# Schematic_Main_Board.net
KiCad netlist of a schematic drawn in Altium Designer
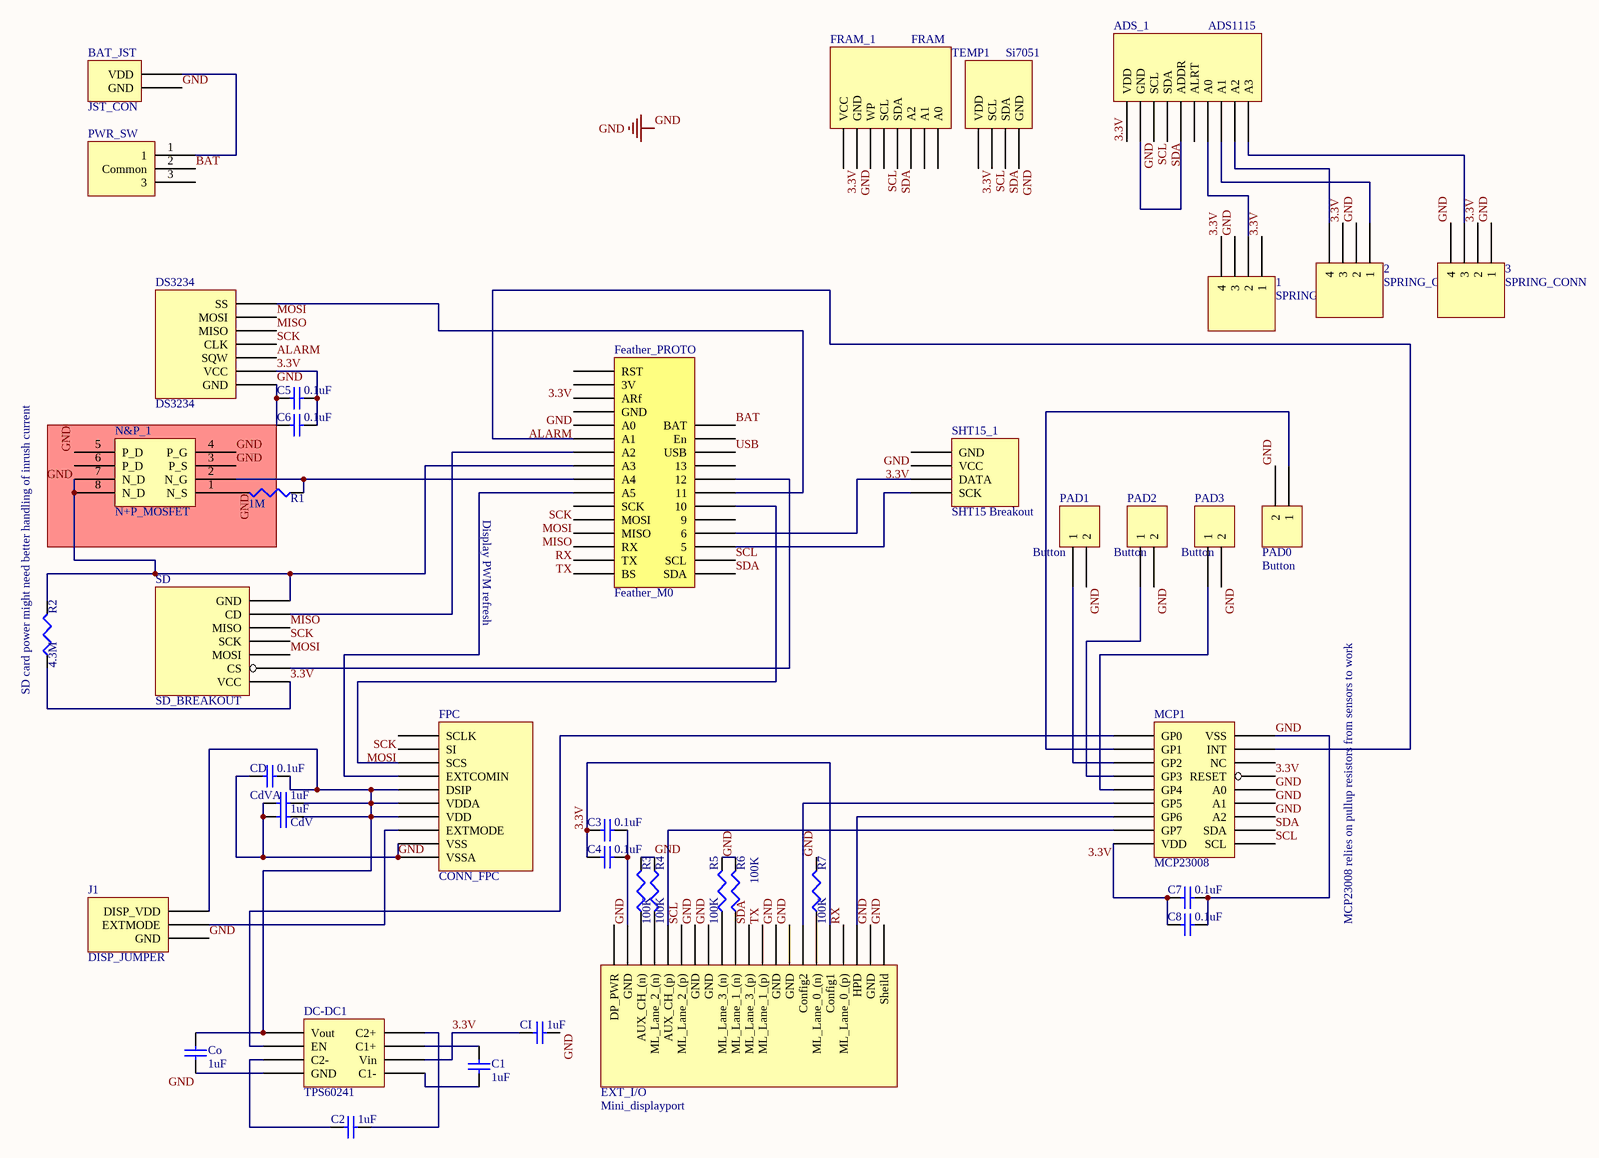
[diagram p0: Schematic_Main_Board.SchDoc]

(export (version "E")
  (design (tool "Eeschema 10.0.6"))
  (components
    (comp (ref "1")
      (value "SPRING_CONN")
      (footprint "QUICK_CONN")
      (libsource (lib "Parts_Schematic") (part "SPRING_CONN"))
    )
    (comp (ref "2")
      (value "SPRING_CONN")
      (footprint "QUICK_CONN")
      (libsource (lib "Parts_Schematic") (part "SPRING_CONN"))
    )
    (comp (ref "3")
      (value "SPRING_CONN")
      (footprint "QUICK_CONN")
      (libsource (lib "Parts_Schematic") (part "SPRING_CONN"))
    )
    (comp (ref "ADS_1")
      (value "ADS1115")
      (footprint "ADS1115")
      (libsource (lib "Parts_Schematic") (part "ADS1115"))
    )
    (comp (ref "BAT_JST")
      (value "JST_CON")
      (footprint "JST_CONN")
      (libsource (lib "Parts_Schematic") (part "JST_CON"))
    )
    (comp (ref "C1")
      (value "1uF")
      (footprint "C0805")
      (description "Capacitor (Semiconductor SIM Model)")
      (fields (field (name "Comment") "Cap Semi") (field (name "PUBLISHER") "Altium Limited"))
      (libsource (lib "Miscellaneous Devices") (part "Cap Semi"))
    )
    (comp (ref "C2")
      (value "1uF")
      (footprint "C0805")
      (description "Capacitor (Semiconductor SIM Model)")
      (fields (field (name "Comment") "Cap Semi") (field (name "PUBLISHER") "Altium Limited"))
      (libsource (lib "Miscellaneous Devices") (part "Cap Semi"))
    )
    (comp (ref "C3")
      (value "0.1uF")
      (footprint "C0805")
      (description "Capacitor (Semiconductor SIM Model)")
      (fields (field (name "Comment") "Cap Semi") (field (name "PUBLISHER") "Altium Limited"))
      (libsource (lib "Miscellaneous Devices") (part "Cap Semi"))
    )
    (comp (ref "C4")
      (value "0.1uF")
      (footprint "C0805")
      (description "Capacitor (Semiconductor SIM Model)")
      (fields (field (name "Comment") "Cap Semi") (field (name "PUBLISHER") "Altium Limited"))
      (libsource (lib "Miscellaneous Devices") (part "Cap Semi"))
    )
    (comp (ref "C5")
      (value "0.1uF")
      (footprint "C0805")
      (description "Capacitor (Semiconductor SIM Model)")
      (fields (field (name "Comment") "Cap Semi") (field (name "PUBLISHER") "Altium Limited"))
      (libsource (lib "Miscellaneous Devices") (part "Cap Semi"))
    )
    (comp (ref "C6")
      (value "0.1uF")
      (footprint "C0805")
      (description "Capacitor (Semiconductor SIM Model)")
      (fields (field (name "Comment") "Cap Semi") (field (name "PUBLISHER") "Altium Limited"))
      (libsource (lib "Miscellaneous Devices") (part "Cap Semi"))
    )
    (comp (ref "C7")
      (value "0.1uF")
      (footprint "C0805")
      (description "Capacitor (Semiconductor SIM Model)")
      (fields (field (name "Comment") "Cap Semi") (field (name "PUBLISHER") "Altium Limited"))
      (libsource (lib "Miscellaneous Devices") (part "Cap Semi"))
    )
    (comp (ref "C8")
      (value "0.1uF")
      (footprint "C0805")
      (description "Capacitor (Semiconductor SIM Model)")
      (fields (field (name "Comment") "Cap Semi") (field (name "PUBLISHER") "Altium Limited"))
      (libsource (lib "Miscellaneous Devices") (part "Cap Semi"))
    )
    (comp (ref "CD")
      (value "0.1uF")
      (footprint "C0805")
      (description "Capacitor (Semiconductor SIM Model)")
      (fields (field (name "Comment") "Cap Semi") (field (name "PUBLISHER") "Altium Limited"))
      (libsource (lib "Miscellaneous Devices") (part "Cap Semi"))
    )
    (comp (ref "CdV")
      (value "1uF")
      (footprint "C0805")
      (description "Capacitor (Semiconductor SIM Model)")
      (fields (field (name "Comment") "Cap Semi") (field (name "PUBLISHER") "Altium Limited"))
      (libsource (lib "Miscellaneous Devices") (part "Cap Semi"))
    )
    (comp (ref "CdVA")
      (value "1uF")
      (footprint "C0805")
      (description "Capacitor (Semiconductor SIM Model)")
      (fields (field (name "Comment") "Cap Semi") (field (name "PUBLISHER") "Altium Limited"))
      (libsource (lib "Miscellaneous Devices") (part "Cap Semi"))
    )
    (comp (ref "CI")
      (value "1uF")
      (footprint "C0805")
      (description "Capacitor (Semiconductor SIM Model)")
      (fields (field (name "Comment") "Cap Semi") (field (name "PUBLISHER") "Altium Limited"))
      (libsource (lib "Miscellaneous Devices") (part "Cap Semi"))
    )
    (comp (ref "Co")
      (value "1uF")
      (footprint "C0805")
      (description "Capacitor (Semiconductor SIM Model)")
      (fields (field (name "Comment") "Cap Semi") (field (name "PUBLISHER") "Altium Limited"))
      (libsource (lib "Miscellaneous Devices") (part "Cap Semi"))
    )
    (comp (ref "DC-DC1")
      (value "TPS60241")
      (footprint "TPS60241")
      (libsource (lib "Parts_Schematic") (part "TPS60241"))
    )
    (comp (ref "DS3234")
      (value "DS3234")
      (footprint "DS3234_FOOTPRINT")
      (libsource (lib "Parts_Schematic") (part "DS3234"))
    )
    (comp (ref "EXT_I/O")
      (value "Mini_displayport")
      (footprint "CONN_Displayport")
      (libsource (lib "Parts_Schematic") (part "Mini_displayport"))
    )
    (comp (ref "Feather_PROTO")
      (value "Feather_M0")
      (footprint "Feather_M0")
      (libsource (lib "Parts_Schematic") (part "Feather_M0"))
    )
    (comp (ref "FPC")
      (value "CONN_FPC")
      (footprint "CONN_FPC")
      (libsource (lib "Parts_Schematic") (part "CONN_FPC"))
    )
    (comp (ref "FRAM_1") (value "FRAM") (footprint "FRAM") (libsource (lib "Parts_Schematic") (part "FRAM")))
    (comp (ref "J1")
      (value "DISP_JUMPER")
      (footprint "DISP_Jumper")
      (libsource (lib "Parts_Schematic") (part "DISP_JUMPER"))
    )
    (comp (ref "MCP1")
      (value "MCP23008")
      (footprint "MCP23008")
      (libsource (lib "Parts_Schematic") (part "MCP23008"))
    )
    (comp (ref "N&P_1")
      (value "N+P_MOSFET")
      (footprint "SOP8")
      (libsource (lib "Parts_Schematic") (part "N+P_MOSFET"))
    )
    (comp (ref "PAD0") (value "Button") (footprint "Button_footprint") (libsource (lib "") (part "Button_1")))
    (comp (ref "PAD1")
      (value "Button")
      (footprint "Button_footprint")
      (libsource (lib "Parts_Schematic") (part "Button"))
    )
    (comp (ref "PAD2")
      (value "Button")
      (footprint "Button_footprint")
      (libsource (lib "Parts_Schematic") (part "Button"))
    )
    (comp (ref "PAD3")
      (value "Button")
      (footprint "Button_footprint")
      (libsource (lib "Parts_Schematic") (part "Button"))
    )
    (comp (ref "PWR_SW")
      (value "Switch")
      (footprint "Switch_footprint")
      (libsource (lib "Parts_Schematic") (part "Switch"))
    )
    (comp (ref "R1")
      (value "1M")
      (footprint "6-0805_N")
      (description "Resistor")
      (fields (field (name "Comment") "Res3") (field (name "PUBLISHER") "Altium Limited"))
      (libsource (lib "Miscellaneous Devices") (part "Res3"))
    )
    (comp (ref "R2")
      (value "4.3M")
      (footprint "6-0805_N")
      (description "Resistor")
      (fields (field (name "Comment") "Res3") (field (name "PUBLISHER") "Altium Limited"))
      (libsource (lib "Miscellaneous Devices") (part "Res3"))
    )
    (comp (ref "R3")
      (value "100K")
      (footprint "6-0805_N")
      (description "Resistor")
      (fields (field (name "Comment") "Res3") (field (name "PUBLISHER") "Altium Limited"))
      (libsource (lib "Miscellaneous Devices") (part "Res3"))
    )
    (comp (ref "R4")
      (value "100K")
      (footprint "6-0805_N")
      (description "Resistor")
      (fields (field (name "Comment") "Res3") (field (name "PUBLISHER") "Altium Limited"))
      (libsource (lib "Miscellaneous Devices") (part "Res3"))
    )
    (comp (ref "R5")
      (value "100K")
      (footprint "6-0805_N")
      (description "Resistor")
      (fields (field (name "Comment") "Res3") (field (name "PUBLISHER") "Altium Limited"))
      (libsource (lib "Miscellaneous Devices") (part "Res3"))
    )
    (comp (ref "R6")
      (value "100K")
      (footprint "6-0805_N")
      (description "Resistor")
      (fields (field (name "Comment") "Res3") (field (name "PUBLISHER") "Altium Limited"))
      (libsource (lib "Miscellaneous Devices") (part "Res3"))
    )
    (comp (ref "R7")
      (value "100K")
      (footprint "6-0805_N")
      (description "Resistor")
      (fields (field (name "Comment") "Res3") (field (name "PUBLISHER") "Altium Limited"))
      (libsource (lib "Miscellaneous Devices") (part "Res3"))
    )
    (comp (ref "SD")
      (value "SD_BREAKOUT")
      (footprint "SD_BREAKOUT_FOOTPRINT")
      (libsource (lib "Parts_Schematic") (part "SD_BREAKOUT"))
    )
    (comp (ref "SHT15_1")
      (value "SHT15 Breakout")
      (footprint "SHT15_BREAKOUT_FOOTPRINT")
      (libsource (lib "Parts_Schematic") (part "SHT15_BREAKOUT"))
    )
    (comp (ref "TEMP1")
      (value "Si7051")
      (footprint "Si7051_Footprint")
      (libsource (lib "Parts_Schematic") (part "Si7051"))
    )
  )
  (nets
    (net (code "1") (name "/3.3V") (class "Default")
      (node (ref "1") (pin "1") (pinfunction "1_1") (pintype "passive"))
      (node (ref "1") (pin "4") (pinfunction "4_4") (pintype "passive"))
      (node (ref "2") (pin "3") (pinfunction "3_3") (pintype "passive"))
      (node (ref "3") (pin "2") (pinfunction "2_2") (pintype "passive"))
      (node (ref "ADS_1") (pin "1") (pinfunction "VDD_1") (pintype "passive"))
      (node (ref "C3") (pin "1") (pinfunction "1_1") (pintype "passive"))
      (node (ref "C4") (pin "2") (pinfunction "2_2") (pintype "passive"))
      (node (ref "C5") (pin "2") (pinfunction "2_2") (pintype "passive"))
      (node (ref "C6") (pin "1") (pinfunction "1_1") (pintype "passive"))
      (node (ref "C7") (pin "1") (pinfunction "1_1") (pintype "passive"))
      (node (ref "C8") (pin "2") (pinfunction "2_2") (pintype "passive"))
      (node (ref "CI") (pin "2") (pinfunction "2_2") (pintype "passive"))
      (node (ref "DC-DC1") (pin "6") (pinfunction "Vin_6") (pintype "passive"))
      (node (ref "DS3234") (pin "2") (pinfunction "VCC_2") (pintype "passive"))
      (node (ref "EXT_I/O") (pin "4") (pinfunction "Config1_4") (pintype "passive"))
      (node (ref "FRAM_1") (pin "1") (pinfunction "VCC_1") (pintype "passive"))
      (node (ref "Feather_PROTO") (pin "2") (pinfunction "3V_2") (pintype "passive"))
      (node (ref "MCP1") (pin "18") (pinfunction "VDD_18") (pintype "passive"))
      (node (ref "MCP1") (pin "6") (pinfunction "RESET_6") (pintype "passive"))
      (node (ref "R2") (pin "1") (pinfunction "1_1") (pintype "passive"))
      (node (ref "SD") (pin "1") (pinfunction "VCC_1") (pintype "passive"))
      (node (ref "SHT15_1") (pin "2") (pinfunction "VCC_2") (pintype "passive"))
      (node (ref "TEMP1") (pin "1") (pinfunction "VDD_1") (pintype "passive"))
    )
    (net (code "2") (name "/ALARM") (class "Default")
      (node (ref "DS3234") (pin "3") (pinfunction "SQW_3") (pintype "passive"))
      (node (ref "Feather_PROTO") (pin "5") (pinfunction "A0_5") (pintype "passive"))
    )
    (net (code "3") (name "/BAT") (class "Default")
      (node (ref "Feather_PROTO") (pin "28") (pinfunction "BAT_28") (pintype "passive"))
      (node (ref "PWR_SW") (pin "2") (pinfunction "Common_2") (pintype "passive"))
    )
    (net (code "4") (name "/MISO") (class "Default")
      (node (ref "DS3234") (pin "5") (pinfunction "MISO_5") (pintype "passive"))
      (node (ref "Feather_PROTO") (pin "13") (pinfunction "MISO_13") (pintype "passive"))
      (node (ref "SD") (pin "5") (pinfunction "MISO_5") (pintype "passive"))
    )
    (net (code "5") (name "/MOSI") (class "Default")
      (node (ref "DS3234") (pin "6") (pinfunction "MOSI_6") (pintype "passive"))
      (node (ref "FPC") (pin "2") (pinfunction "SI_2") (pintype "passive"))
      (node (ref "Feather_PROTO") (pin "12") (pinfunction "MOSI_12") (pintype "passive"))
      (node (ref "SD") (pin "3") (pinfunction "MOSI_3") (pintype "passive"))
    )
    (net (code "6") (name "/RX") (class "Default")
      (node (ref "EXT_I/O") (pin "3") (pinfunction "ML_Lane_0_(p)_3") (pintype "passive"))
      (node (ref "Feather_PROTO") (pin "14") (pinfunction "RX_14") (pintype "passive"))
    )
    (net (code "7") (name "/SCK") (class "Default")
      (node (ref "DS3234") (pin "4") (pinfunction "CLK_4") (pintype "passive"))
      (node (ref "FPC") (pin "1") (pinfunction "SCLK_1") (pintype "passive"))
      (node (ref "Feather_PROTO") (pin "11") (pinfunction "SCK_11") (pintype "passive"))
      (node (ref "SD") (pin "4") (pinfunction "SCK_4") (pintype "passive"))
    )
    (net (code "8") (name "/SCL") (class "Default")
      (node (ref "ADS_1") (pin "3") (pinfunction "SCL_3") (pintype "passive"))
      (node (ref "EXT_I/O") (pin "15") (pinfunction "ML_Lane_2_(p)_15") (pintype "passive"))
      (node (ref "FRAM_1") (pin "4") (pinfunction "SCL_4") (pintype "passive"))
      (node (ref "Feather_PROTO") (pin "18") (pinfunction "SCL_18") (pintype "passive"))
      (node (ref "MCP1") (pin "1") (pinfunction "SCL_1") (pintype "passive"))
      (node (ref "TEMP1") (pin "2") (pinfunction "SCL_2") (pintype "passive"))
    )
    (net (code "9") (name "/SDA") (class "Default")
      (node (ref "ADS_1") (pin "4") (pinfunction "SDA_4") (pintype "passive"))
      (node (ref "EXT_I/O") (pin "10") (pinfunction "ML_Lane_3_(p)_10") (pintype "passive"))
      (node (ref "FRAM_1") (pin "5") (pinfunction "SDA_5") (pintype "passive"))
      (node (ref "Feather_PROTO") (pin "17") (pinfunction "SDA_17") (pintype "passive"))
      (node (ref "MCP1") (pin "2") (pinfunction "SDA_2") (pintype "passive"))
      (node (ref "TEMP1") (pin "3") (pinfunction "SDA_3") (pintype "passive"))
    )
    (net (code "10") (name "/TX") (class "Default")
      (node (ref "EXT_I/O") (pin "9") (pinfunction "ML_Lane_1_(p)_9") (pintype "passive"))
      (node (ref "Feather_PROTO") (pin "15") (pinfunction "TX_15") (pintype "passive"))
    )
    (net (code "11") (name "/USB") (class "Default")
      (node (ref "Feather_PROTO") (pin "26") (pinfunction "USB_26") (pintype "passive"))
    )
    (net (code "12") (name "GND") (class "Default")
      (node (ref "1") (pin "3") (pinfunction "3_3") (pintype "passive"))
      (node (ref "2") (pin "2") (pinfunction "2_2") (pintype "passive"))
      (node (ref "3") (pin "1") (pinfunction "1_1") (pintype "passive"))
      (node (ref "3") (pin "4") (pinfunction "4_4") (pintype "passive"))
      (node (ref "ADS_1") (pin "2") (pinfunction "GND_2") (pintype "passive"))
      (node (ref "ADS_1") (pin "5") (pinfunction "ADDR_5") (pintype "passive"))
      (node (ref "BAT_JST") (pin "1") (pinfunction "GND_1") (pintype "passive"))
      (node (ref "C3") (pin "2") (pinfunction "2_2") (pintype "passive"))
      (node (ref "C4") (pin "1") (pinfunction "1_1") (pintype "passive"))
      (node (ref "C5") (pin "1") (pinfunction "1_1") (pintype "passive"))
      (node (ref "C6") (pin "2") (pinfunction "2_2") (pintype "passive"))
      (node (ref "C7") (pin "2") (pinfunction "2_2") (pintype "passive"))
      (node (ref "C8") (pin "1") (pinfunction "1_1") (pintype "passive"))
      (node (ref "CD") (pin "2") (pinfunction "2_2") (pintype "passive"))
      (node (ref "CI") (pin "1") (pinfunction "1_1") (pintype "passive"))
      (node (ref "CdV") (pin "2") (pinfunction "2_2") (pintype "passive"))
      (node (ref "CdVA") (pin "2") (pinfunction "2_2") (pintype "passive"))
      (node (ref "Co") (pin "2") (pinfunction "2_2") (pintype "passive"))
      (node (ref "DC-DC1") (pin "4") (pinfunction "GND_4") (pintype "passive"))
      (node (ref "DS3234") (pin "1") (pinfunction "GND_1") (pintype "passive"))
      (node (ref "EXT_I/O") (pin "0") (pinfunction "Sheild_0") (pintype "passive"))
      (node (ref "EXT_I/O") (pin "1") (pinfunction "GND_1") (pintype "passive"))
      (node (ref "EXT_I/O") (pin "13") (pinfunction "GND_13") (pintype "passive"))
      (node (ref "EXT_I/O") (pin "14") (pinfunction "GND_14") (pintype "passive"))
      (node (ref "EXT_I/O") (pin "19") (pinfunction "GND_19") (pintype "passive"))
      (node (ref "EXT_I/O") (pin "7") (pinfunction "GND_7") (pintype "passive"))
      (node (ref "EXT_I/O") (pin "8") (pinfunction "GND_8") (pintype "passive"))
      (node (ref "FPC") (pin "10") (pinfunction "VSSA_10") (pintype "passive"))
      (node (ref "FPC") (pin "9") (pinfunction "VSS_9") (pintype "passive"))
      (node (ref "FRAM_1") (pin "2") (pinfunction "GND_2") (pintype "passive"))
      (node (ref "Feather_PROTO") (pin "4") (pinfunction "GND_4") (pintype "passive"))
      (node (ref "J1") (pin "1") (pinfunction "GND_1") (pintype "passive"))
      (node (ref "MCP1") (pin "3") (pinfunction "A2_3") (pintype "passive"))
      (node (ref "MCP1") (pin "4") (pinfunction "A1_4") (pintype "passive"))
      (node (ref "MCP1") (pin "5") (pinfunction "A0_5") (pintype "passive"))
      (node (ref "MCP1") (pin "9") (pinfunction "VSS_9") (pintype "passive"))
      (node (ref "N&P_1") (pin "1") (pinfunction "N_S_1") (pintype "passive"))
      (node (ref "N&P_1") (pin "3") (pinfunction "P_S_3") (pintype "passive"))
      (node (ref "N&P_1") (pin "4") (pinfunction "P_G_4") (pintype "passive"))
      (node (ref "N&P_1") (pin "5") (pinfunction "P_D_5") (pintype "passive"))
      (node (ref "N&P_1") (pin "6") (pinfunction "P_D_6") (pintype "passive"))
      (node (ref "PAD0") (pin "2") (pinfunction "2_2") (pintype "passive"))
      (node (ref "PAD1") (pin "2") (pinfunction "2_2") (pintype "passive"))
      (node (ref "PAD2") (pin "2") (pinfunction "2_2") (pintype "passive"))
      (node (ref "PAD3") (pin "2") (pinfunction "2_2") (pintype "passive"))
      (node (ref "R1") (pin "2") (pinfunction "2_2") (pintype "passive"))
      (node (ref "R3") (pin "2") (pinfunction "2_2") (pintype "passive"))
      (node (ref "R4") (pin "1") (pinfunction "1_1") (pintype "passive"))
      (node (ref "R5") (pin "2") (pinfunction "2_2") (pintype "passive"))
      (node (ref "R6") (pin "2") (pinfunction "2_2") (pintype "passive"))
      (node (ref "R7") (pin "2") (pinfunction "2_2") (pintype "passive"))
      (node (ref "SHT15_1") (pin "1") (pinfunction "GND_1") (pintype "passive"))
      (node (ref "TEMP1") (pin "4") (pinfunction "GND_4") (pintype "passive"))
    )
    (net (code "13") (name "Net-(ADS_1-A0)") (class "Default")
      (node (ref "1") (pin "2") (pinfunction "2_2") (pintype "passive"))
      (node (ref "ADS_1") (pin "7") (pinfunction "A0_7") (pintype "passive"))
    )
    (net (code "14") (name "Net-(ADS_1-A1)") (class "Default")
      (node (ref "2") (pin "1") (pinfunction "1_1") (pintype "passive"))
      (node (ref "ADS_1") (pin "8") (pinfunction "A1_8") (pintype "passive"))
    )
    (net (code "15") (name "Net-(ADS_1-A2)") (class "Default")
      (node (ref "2") (pin "4") (pinfunction "4_4") (pintype "passive"))
      (node (ref "ADS_1") (pin "9") (pinfunction "A2_9") (pintype "passive"))
    )
    (net (code "16") (name "Net-(ADS_1-A3)") (class "Default")
      (node (ref "3") (pin "3") (pinfunction "3_3") (pintype "passive"))
      (node (ref "ADS_1") (pin "10") (pinfunction "A3_10") (pintype "passive"))
    )
    (net (code "17") (name "Net-(BAT_JST-VDD)") (class "Default")
      (node (ref "BAT_JST") (pin "2") (pinfunction "VDD_2") (pintype "passive"))
      (node (ref "PWR_SW") (pin "1") (pinfunction "1_1") (pintype "passive"))
    )
    (net (code "18") (name "Net-(DC-DC1-C1+)") (class "Default")
      (node (ref "C1") (pin "1") (pinfunction "1_1") (pintype "passive"))
      (node (ref "DC-DC1") (pin "7") (pinfunction "C1+_7") (pintype "passive"))
    )
    (net (code "19") (name "Net-(DC-DC1-C1-)") (class "Default")
      (node (ref "C1") (pin "2") (pinfunction "2_2") (pintype "passive"))
      (node (ref "DC-DC1") (pin "5") (pinfunction "C1-_5") (pintype "passive"))
    )
    (net (code "20") (name "Net-(DC-DC1-C2+)") (class "Default")
      (node (ref "C2") (pin "1") (pinfunction "1_1") (pintype "passive"))
      (node (ref "DC-DC1") (pin "8") (pinfunction "C2+_8") (pintype "passive"))
    )
    (net (code "21") (name "Net-(DC-DC1-C2-)") (class "Default")
      (node (ref "C2") (pin "2") (pinfunction "2_2") (pintype "passive"))
      (node (ref "DC-DC1") (pin "3") (pinfunction "C2-_3") (pintype "passive"))
    )
    (net (code "22") (name "Net-(DC-DC1-EN)") (class "Default")
      (node (ref "DC-DC1") (pin "2") (pinfunction "EN_2") (pintype "passive"))
      (node (ref "MCP1") (pin "10") (pinfunction "GP0_10") (pintype "passive"))
    )
    (net (code "23") (name "Net-(DC-DC1-Vout)") (class "Default")
      (node (ref "CD") (pin "1") (pinfunction "1_1") (pintype "passive"))
      (node (ref "CdV") (pin "1") (pinfunction "1_1") (pintype "passive"))
      (node (ref "CdVA") (pin "1") (pinfunction "1_1") (pintype "passive"))
      (node (ref "Co") (pin "1") (pinfunction "1_1") (pintype "passive"))
      (node (ref "DC-DC1") (pin "1") (pinfunction "Vout_1") (pintype "passive"))
      (node (ref "FPC") (pin "5") (pinfunction "DSIP_5") (pintype "passive"))
      (node (ref "FPC") (pin "6") (pinfunction "VDDA_6") (pintype "passive"))
      (node (ref "FPC") (pin "7") (pinfunction "VDD_7") (pintype "passive"))
      (node (ref "J1") (pin "3") (pinfunction "DISP_VDD_3") (pintype "passive"))
    )
    (net (code "24") (name "Net-(DS3234-SS)") (class "Default")
      (node (ref "DS3234") (pin "7") (pinfunction "SS_7") (pintype "passive"))
      (node (ref "Feather_PROTO") (pin "23") (pinfunction "11_23") (pintype "passive"))
    )
    (net (code "25") (name "Net-(EXT_I/O-AUX_CH_(n))") (class "Default")
      (node (ref "EXT_I/O") (pin "18") (pinfunction "AUX_CH_(n)_18") (pintype "passive"))
      (node (ref "R3") (pin "1") (pinfunction "1_1") (pintype "passive"))
    )
    (net (code "26") (name "Net-(EXT_I/O-AUX_CH_(p))") (class "Default")
      (node (ref "EXT_I/O") (pin "16") (pinfunction "AUX_CH_(p)_16") (pintype "passive"))
      (node (ref "MCP1") (pin "17") (pinfunction "GP7_17") (pintype "passive"))
    )
    (net (code "27") (name "Net-(EXT_I/O-Config2)") (class "Default")
      (node (ref "EXT_I/O") (pin "6") (pinfunction "Config2_6") (pintype "passive"))
      (node (ref "MCP1") (pin "15") (pinfunction "GP5_15") (pintype "passive"))
    )
    (net (code "28") (name "Net-(EXT_I/O-HPD)") (class "Default")
      (node (ref "EXT_I/O") (pin "2") (pinfunction "HPD_2") (pintype "passive"))
      (node (ref "MCP1") (pin "16") (pinfunction "GP6_16") (pintype "passive"))
    )
    (net (code "29") (name "Net-(EXT_I/O-ML_Lane_0_(n))") (class "Default")
      (node (ref "EXT_I/O") (pin "5") (pinfunction "ML_Lane_0_(n)_5") (pintype "passive"))
      (node (ref "R7") (pin "1") (pinfunction "1_1") (pintype "passive"))
    )
    (net (code "30") (name "Net-(EXT_I/O-ML_Lane_1_(n))") (class "Default")
      (node (ref "EXT_I/O") (pin "11") (pinfunction "ML_Lane_1_(n)_11") (pintype "passive"))
      (node (ref "R6") (pin "1") (pinfunction "1_1") (pintype "passive"))
    )
    (net (code "31") (name "Net-(EXT_I/O-ML_Lane_2_(n))") (class "Default")
      (node (ref "EXT_I/O") (pin "17") (pinfunction "ML_Lane_2_(n)_17") (pintype "passive"))
      (node (ref "R4") (pin "2") (pinfunction "2_2") (pintype "passive"))
    )
    (net (code "32") (name "Net-(EXT_I/O-ML_Lane_3_(n))") (class "Default")
      (node (ref "EXT_I/O") (pin "12") (pinfunction "ML_Lane_3_(n)_12") (pintype "passive"))
      (node (ref "R5") (pin "1") (pinfunction "1_1") (pintype "passive"))
    )
    (net (code "33") (name "Net-(FPC-EXTCOMIN)") (class "Default")
      (node (ref "FPC") (pin "4") (pinfunction "EXTCOMIN_4") (pintype "passive"))
      (node (ref "Feather_PROTO") (pin "10") (pinfunction "A5_10") (pintype "passive"))
    )
    (net (code "34") (name "Net-(FPC-EXTMODE)") (class "Default")
      (node (ref "FPC") (pin "8") (pinfunction "EXTMODE_8") (pintype "passive"))
      (node (ref "J1") (pin "2") (pinfunction "EXTMODE_2") (pintype "passive"))
    )
    (net (code "35") (name "Net-(FPC-SCS)") (class "Default")
      (node (ref "FPC") (pin "3") (pinfunction "SCS_3") (pintype "passive"))
      (node (ref "Feather_PROTO") (pin "22") (pinfunction "10_22") (pintype "passive"))
    )
    (net (code "36") (name "Net-(Feather_PROTO-5)") (class "Default")
      (node (ref "Feather_PROTO") (pin "19") (pinfunction "5_19") (pintype "passive"))
      (node (ref "SHT15_1") (pin "4") (pinfunction "SCK_4") (pintype "passive"))
    )
    (net (code "37") (name "Net-(Feather_PROTO-6)") (class "Default")
      (node (ref "Feather_PROTO") (pin "20") (pinfunction "6_20") (pintype "passive"))
      (node (ref "SHT15_1") (pin "3") (pinfunction "DATA_3") (pintype "passive"))
    )
    (net (code "38") (name "Net-(Feather_PROTO-12)") (class "Default")
      (node (ref "Feather_PROTO") (pin "24") (pinfunction "12_24") (pintype "passive"))
      (node (ref "SD") (pin "2") (pinfunction "CS_2") (pintype "passive"))
    )
    (net (code "39") (name "Net-(Feather_PROTO-A1)") (class "Default")
      (node (ref "Feather_PROTO") (pin "6") (pinfunction "A1_6") (pintype "passive"))
      (node (ref "MCP1") (pin "8") (pinfunction "INT_8") (pintype "passive"))
    )
    (net (code "40") (name "Net-(Feather_PROTO-A2)") (class "Default")
      (node (ref "Feather_PROTO") (pin "7") (pinfunction "A2_7") (pintype "passive"))
      (node (ref "SD") (pin "6") (pinfunction "CD_6") (pintype "passive"))
    )
    (net (code "41") (name "Net-(Feather_PROTO-A3)") (class "Default")
      (node (ref "Feather_PROTO") (pin "8") (pinfunction "A3_8") (pintype "passive"))
      (node (ref "N&P_1") (pin "7") (pinfunction "N_D_7") (pintype "passive"))
      (node (ref "N&P_1") (pin "8") (pinfunction "N_D_8") (pintype "passive"))
      (node (ref "R2") (pin "2") (pinfunction "2_2") (pintype "passive"))
      (node (ref "SD") (pin "7") (pinfunction "GND_7") (pintype "passive"))
    )
    (net (code "42") (name "Net-(Feather_PROTO-A4)") (class "Default")
      (node (ref "Feather_PROTO") (pin "9") (pinfunction "A4_9") (pintype "passive"))
      (node (ref "N&P_1") (pin "2") (pinfunction "N_G_2") (pintype "passive"))
      (node (ref "R1") (pin "1") (pinfunction "1_1") (pintype "passive"))
    )
    (net (code "43") (name "Net-(MCP1-GP1)") (class "Default")
      (node (ref "MCP1") (pin "11") (pinfunction "GP1_11") (pintype "passive"))
      (node (ref "PAD0") (pin "1") (pinfunction "1_1") (pintype "passive"))
    )
    (net (code "44") (name "Net-(MCP1-GP2)") (class "Default")
      (node (ref "MCP1") (pin "12") (pinfunction "GP2_12") (pintype "passive"))
      (node (ref "PAD1") (pin "1") (pinfunction "1_1") (pintype "passive"))
    )
    (net (code "45") (name "Net-(MCP1-GP3)") (class "Default")
      (node (ref "MCP1") (pin "13") (pinfunction "GP3_13") (pintype "passive"))
      (node (ref "PAD2") (pin "1") (pinfunction "1_1") (pintype "passive"))
    )
    (net (code "46") (name "Net-(MCP1-GP4)") (class "Default")
      (node (ref "MCP1") (pin "14") (pinfunction "GP4_14") (pintype "passive"))
      (node (ref "PAD3") (pin "1") (pinfunction "1_1") (pintype "passive"))
    )
    (net (code "47") (name "unconnected-(ADS_1-ALRT-Pad6)") (class "Default")
      (node (ref "ADS_1") (pin "6") (pinfunction "ALRT_6") (pintype "passive"))
    )
    (net (code "48") (name "unconnected-(EXT_I/O-DP_PWR-Pad20)") (class "Default")
      (node (ref "EXT_I/O") (pin "20") (pinfunction "DP_PWR_20") (pintype "passive"))
    )
    (net (code "49") (name "unconnected-(FRAM_1-A0-Pad8)") (class "Default")
      (node (ref "FRAM_1") (pin "8") (pinfunction "A0_8") (pintype "passive"))
    )
    (net (code "50") (name "unconnected-(FRAM_1-A1-Pad7)") (class "Default")
      (node (ref "FRAM_1") (pin "7") (pinfunction "A1_7") (pintype "passive"))
    )
    (net (code "51") (name "unconnected-(FRAM_1-A2-Pad6)") (class "Default")
      (node (ref "FRAM_1") (pin "6") (pinfunction "A2_6") (pintype "passive"))
    )
    (net (code "52") (name "unconnected-(FRAM_1-WP-Pad3)") (class "Default")
      (node (ref "FRAM_1") (pin "3") (pinfunction "WP_3") (pintype "passive"))
    )
    (net (code "53") (name "unconnected-(Feather_PROTO-9-Pad21)") (class "Default")
      (node (ref "Feather_PROTO") (pin "21") (pinfunction "9_21") (pintype "passive"))
    )
    (net (code "54") (name "unconnected-(Feather_PROTO-13-Pad25)") (class "Default")
      (node (ref "Feather_PROTO") (pin "25") (pinfunction "13_25") (pintype "passive"))
    )
    (net (code "55") (name "unconnected-(Feather_PROTO-ARf-Pad3)") (class "Default")
      (node (ref "Feather_PROTO") (pin "3") (pinfunction "ARf_3") (pintype "passive"))
    )
    (net (code "56") (name "unconnected-(Feather_PROTO-BS-Pad16)") (class "Default")
      (node (ref "Feather_PROTO") (pin "16") (pinfunction "BS_16") (pintype "passive"))
    )
    (net (code "57") (name "unconnected-(Feather_PROTO-En-Pad27)") (class "Default")
      (node (ref "Feather_PROTO") (pin "27") (pinfunction "En_27") (pintype "passive"))
    )
    (net (code "58") (name "unconnected-(Feather_PROTO-RST-Pad1)") (class "Default")
      (node (ref "Feather_PROTO") (pin "1") (pinfunction "RST_1") (pintype "passive"))
    )
    (net (code "59") (name "unconnected-(MCP1-NC-Pad7)") (class "Default")
      (node (ref "MCP1") (pin "7") (pinfunction "NC_7") (pintype "passive"))
    )
    (net (code "60") (name "unconnected-(PWR_SW-Pad3)") (class "Default")
      (node (ref "PWR_SW") (pin "3") (pinfunction "3_3") (pintype "passive"))
    )
  )
)
